# USB3_Interface.net
KiCad netlist of a schematic drawn in Altium Designer
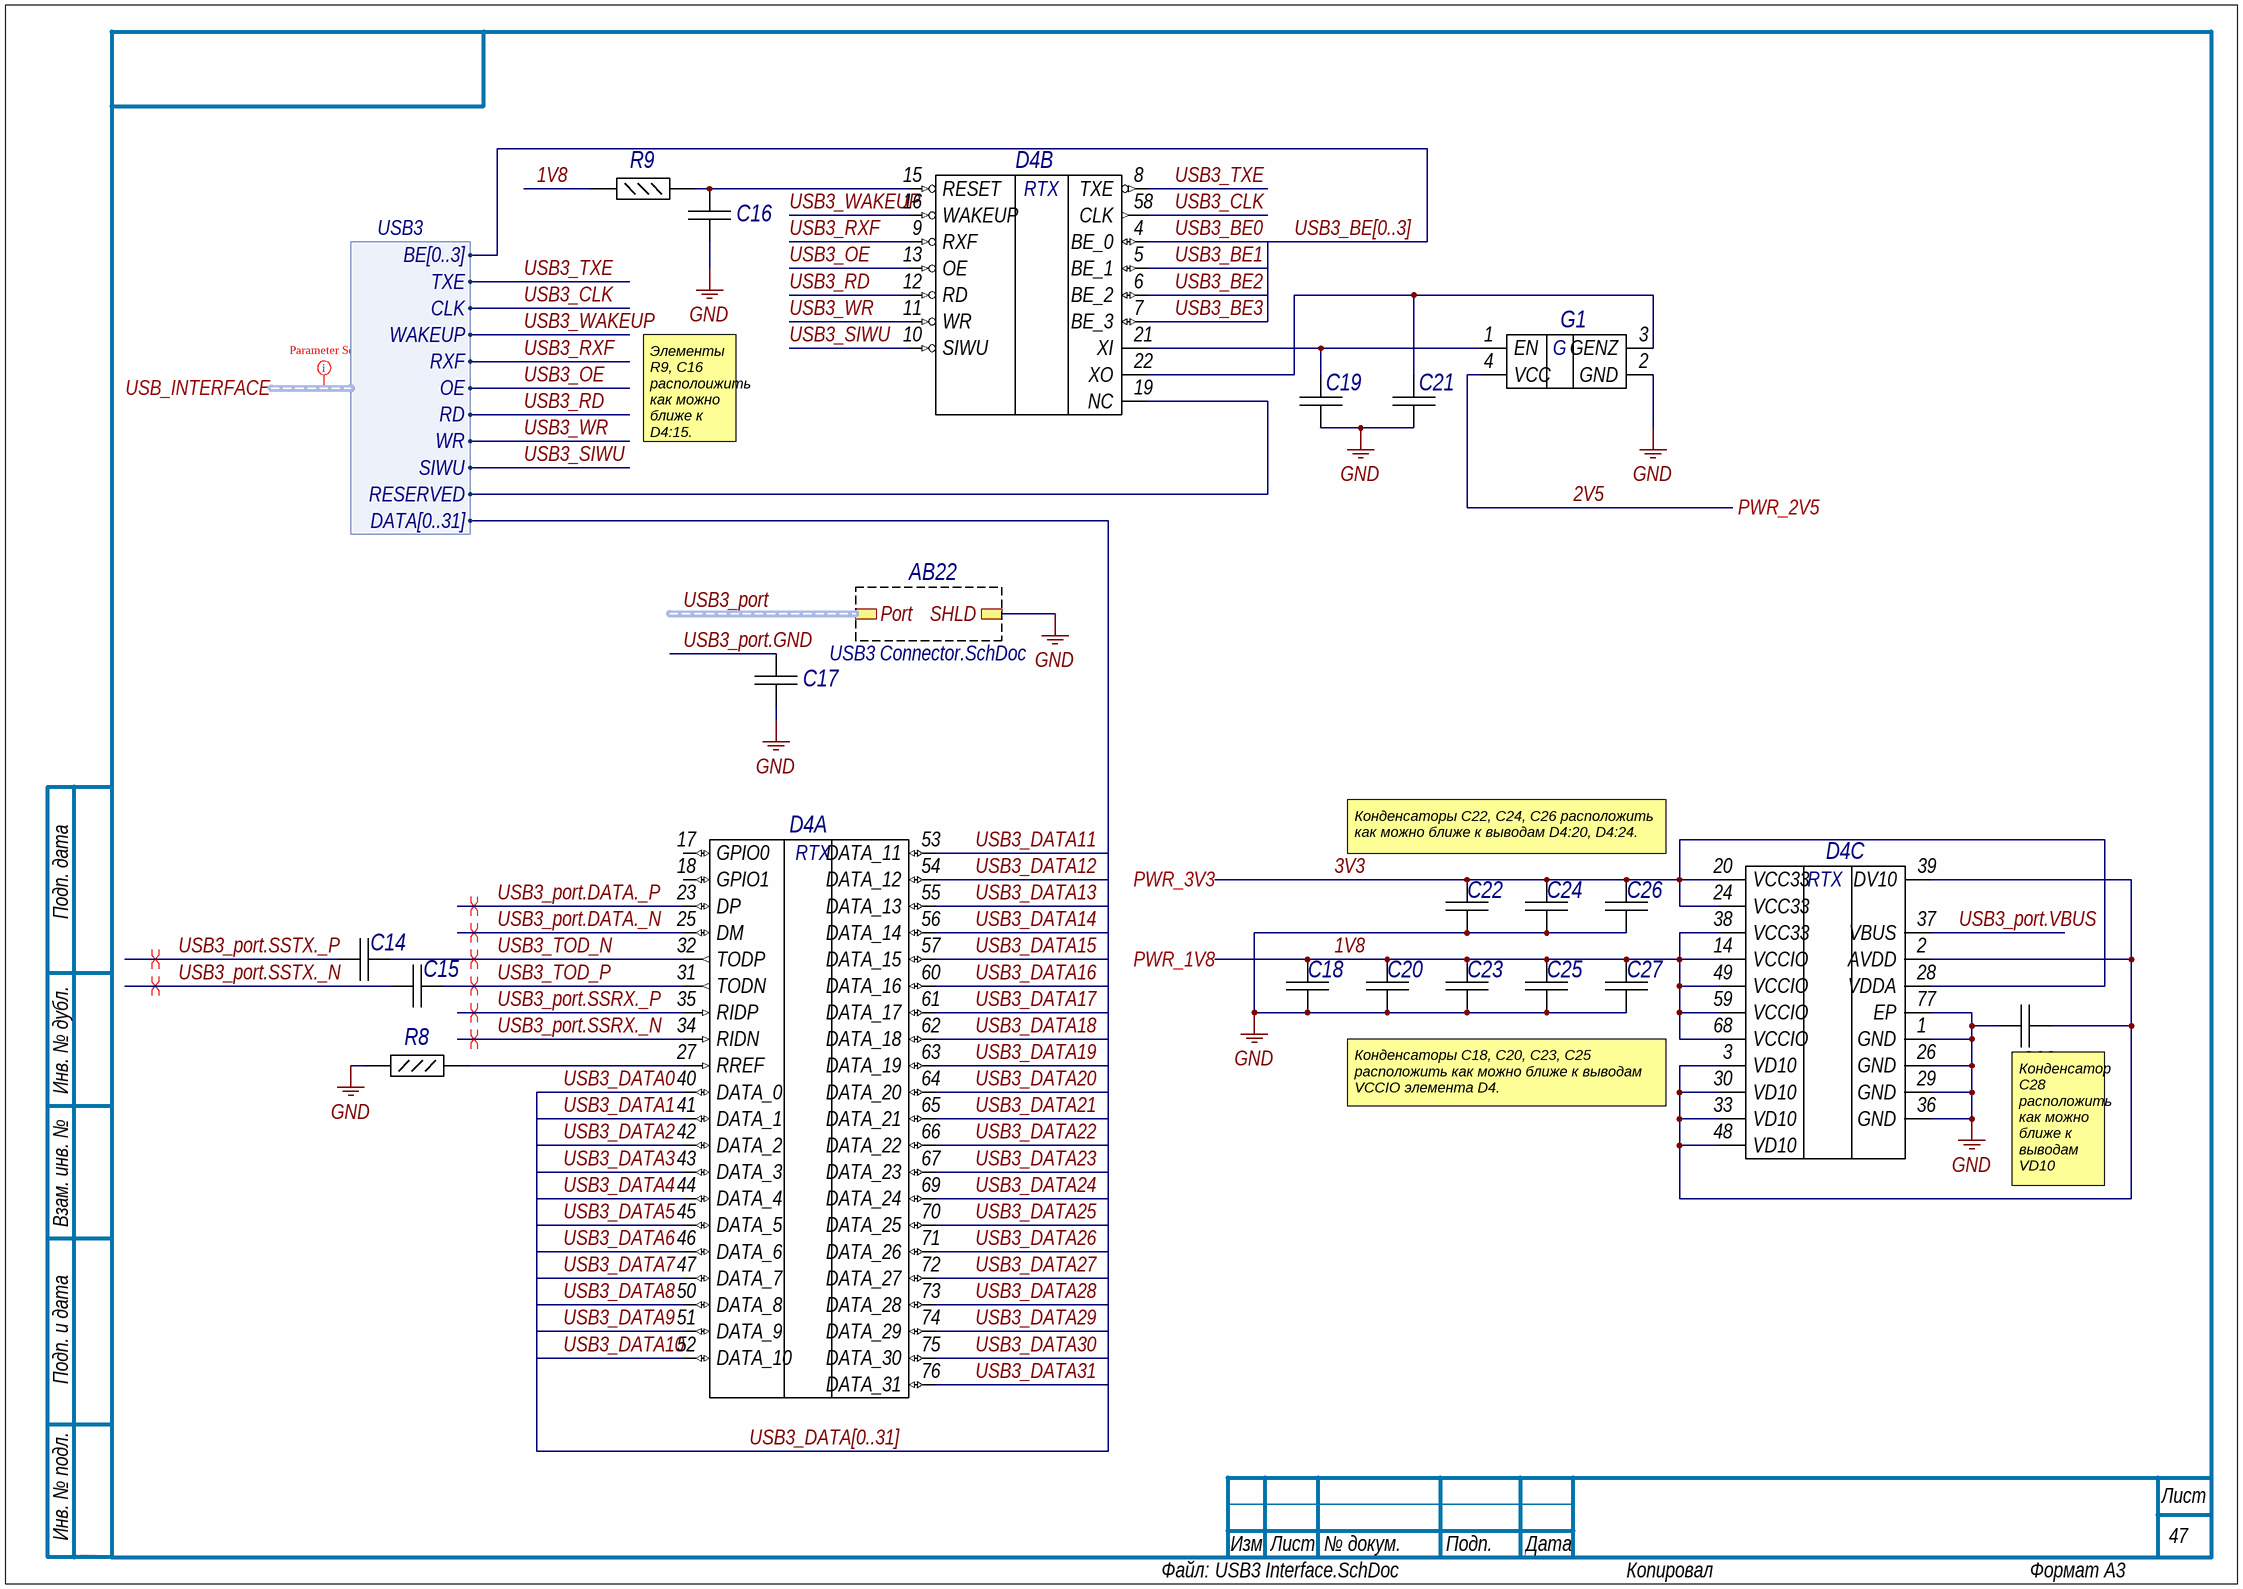
[diagram p0: USB3 Interface.SchDoc]

(export (version "E")
  (design (tool "Eeschema 10.0.6"))
  (components
    (comp (ref "C14")
      (value "GRM033R60J104KE19D")
      (footprint "CAPC0603X33X15LL03T05")
      (description "Chip Capacitor, 100 nF, +/- 10%, 6.3 V, -55 to 85 degC, 0201 (0603 Metric), RoHS, Tape and Reel")
      (fields (field (name "TOLERANCE") "10%") (field (name "MANUFACTURER") "Basic Passives"))
      (libsource (lib "MiniPC DB") (part "CAP_NP"))
    )
    (comp (ref "C15")
      (value "GRM033R60J104KE19D")
      (footprint "CAPC0603X33X15LL03T05")
      (description "Chip Capacitor, 100 nF, +/- 10%, 6.3 V, -55 to 85 degC, 0201 (0603 Metric), RoHS, Tape and Reel")
      (fields (field (name "TOLERANCE") "10%") (field (name "MANUFACTURER") "Basic Passives"))
      (libsource (lib "MiniPC DB") (part "CAP_NP"))
    )
    (comp (ref "C16")
      (value "GRM033R60J104KE19D")
      (footprint "CAPC0603X33X15LL03T05")
      (description "Chip Capacitor, 100 nF, +/- 10%, 6.3 V, -55 to 85 degC, 0201 (0603 Metric), RoHS, Tape and Reel")
      (fields (field (name "TOLERANCE") "10%") (field (name "MANUFACTURER") "Basic Passives"))
      (libsource (lib "MiniPC DB") (part "CAP_NP"))
    )
    (comp (ref "C17")
      (value "GRM033R60J104KE19D")
      (footprint "CAPC0603X33X15LL03T05")
      (description "Chip Capacitor, 100 nF, +/- 10%, 6.3 V, -55 to 85 degC, 0201 (0603 Metric), RoHS, Tape and Reel")
      (fields (field (name "TOLERANCE") "10%") (field (name "MANUFACTURER") "Basic Passives"))
      (libsource (lib "MiniPC DB") (part "CAP_NP"))
    )
    (comp (ref "C18")
      (value "C1005X7R1E104M")
      (footprint "CAPC1005X55X10LL05")
      (description "Chip Capacitor, 0.1 uF, +/- 20%, 25 V, -55 to 125 degC, 0402 (1005 Metric), RoHS, Tape and Reel")
      (fields (field (name "TOLERANCE") "20%"))
      (libsource (lib "MiniPC DB") (part "CAP_NP"))
    )
    (comp (ref "C19")
      (value "GRM033R60J104KE19D")
      (footprint "CAPC0603X33X15LL03T05")
      (description "Chip Capacitor, 100 nF, +/- 10%, 6.3 V, -55 to 85 degC, 0201 (0603 Metric), RoHS, Tape and Reel")
      (fields (field (name "TOLERANCE") "10%") (field (name "MANUFACTURER") "Basic Passives"))
      (libsource (lib "MiniPC DB") (part "CAP_NP"))
    )
    (comp (ref "C20")
      (value "C1005X7R1E104M")
      (footprint "CAPC1005X55X10LL05")
      (description "Chip Capacitor, 0.1 uF, +/- 20%, 25 V, -55 to 125 degC, 0402 (1005 Metric), RoHS, Tape and Reel")
      (fields (field (name "TOLERANCE") "20%"))
      (libsource (lib "MiniPC DB") (part "CAP_NP"))
    )
    (comp (ref "C21")
      (value "GRM033R60J104KE19D")
      (footprint "CAPC0603X33X15LL03T05")
      (description "Chip Capacitor, 100 nF, +/- 10%, 6.3 V, -55 to 85 degC, 0201 (0603 Metric), RoHS, Tape and Reel")
      (fields (field (name "TOLERANCE") "10%") (field (name "MANUFACTURER") "Basic Passives"))
      (libsource (lib "MiniPC DB") (part "CAP_NP"))
    )
    (comp (ref "C22")
      (value "C1005X7R1E104M")
      (footprint "CAPC1005X55X10LL05")
      (description "Chip Capacitor, 0.1 uF, +/- 20%, 25 V, -55 to 125 degC, 0402 (1005 Metric), RoHS, Tape and Reel")
      (fields (field (name "TOLERANCE") "20%"))
      (libsource (lib "MiniPC DB") (part "CAP_NP"))
    )
    (comp (ref "C23")
      (value "C1005X7R1E104M")
      (footprint "CAPC1005X55X10LL05")
      (description "Chip Capacitor, 0.1 uF, +/- 20%, 25 V, -55 to 125 degC, 0402 (1005 Metric), RoHS, Tape and Reel")
      (fields (field (name "TOLERANCE") "20%"))
      (libsource (lib "MiniPC DB") (part "CAP_NP"))
    )
    (comp (ref "C24")
      (value "C1005X7R1E104M")
      (footprint "CAPC1005X55X10LL05")
      (description "Chip Capacitor, 0.1 uF, +/- 20%, 25 V, -55 to 125 degC, 0402 (1005 Metric), RoHS, Tape and Reel")
      (fields (field (name "TOLERANCE") "20%"))
      (libsource (lib "MiniPC DB") (part "CAP_NP"))
    )
    (comp (ref "C25")
      (value "C1005X7R1E104M")
      (footprint "CAPC1005X55X10LL05")
      (description "Chip Capacitor, 0.1 uF, +/- 20%, 25 V, -55 to 125 degC, 0402 (1005 Metric), RoHS, Tape and Reel")
      (fields (field (name "TOLERANCE") "20%"))
      (libsource (lib "MiniPC DB") (part "CAP_NP"))
    )
    (comp (ref "C26")
      (value "C1005X7R1E104M")
      (footprint "CAPC1005X55X10LL05")
      (description "Chip Capacitor, 0.1 uF, +/- 20%, 25 V, -55 to 125 degC, 0402 (1005 Metric), RoHS, Tape and Reel")
      (fields (field (name "TOLERANCE") "20%"))
      (libsource (lib "MiniPC DB") (part "CAP_NP"))
    )
    (comp (ref "C27")
      (value "C1005X7R1E104M")
      (footprint "CAPC1005X55X10LL05")
      (description "Chip Capacitor, 0.1 uF, +/- 20%, 25 V, -55 to 125 degC, 0402 (1005 Metric), RoHS, Tape and Reel")
      (fields (field (name "TOLERANCE") "20%"))
      (libsource (lib "MiniPC DB") (part "CAP_NP"))
    )
    (comp (ref "C28")
      (value "GRM033R60J104KE19D")
      (footprint "CAPC0603X33X15LL03T05")
      (description "Chip Capacitor, 100 nF, +/- 10%, 6.3 V, -55 to 85 degC, 0201 (0603 Metric), RoHS, Tape and Reel")
      (fields (field (name "TOLERANCE") "10%") (field (name "MANUFACTURER") "Basic Passives"))
      (libsource (lib "MiniPC DB") (part "CAP_NP"))
    )
    (comp (ref "D4")
      (value "FT601Q")
      (footprint "FTDI-QFN-76_M")
      (description "32 Bit USB 3.0 to FIFO Bridge, 5 Gbps, 3 to 3.6 V, -40 to 85 degC, 76-Pin QFN, Pb-Free")
      (libsource (lib "") (part "FT601Q_1"))
    )
    (comp (ref "G1")
      (value "ASE2-33.000MHZ-ET")
      (footprint "ABRA-ASE2_V")
      (fields (field (name "MANUFACTURER") "Abracon"))
      (libsource (lib "MiniPC DB") (part "ASE2"))
    )
    (comp (ref "R8")
      (value "ERJ-2RKF1651X")
      (footprint "RESC1005X40X25LL05T05")
      (description "Chip Resistor, 1.65 KOhm, +/- 1%, 100 mW, -55 to 155 degC, 0402 (1005 Metric), RoHS, Tape and Reel")
      (fields (field (name "TOLERANCE") "1%") (field (name "MANUFACTURER") "Basic Passives"))
      (libsource (lib "") (part "RES-0.05_1"))
    )
    (comp (ref "R9")
      (value "ERJ-2RKF1002X")
      (footprint "RESC1005X40X25LL05T05")
      (description "Chip Resistor, 10 KOhm, +/- 1%, 100 mW, -55 to 155 degC, 0402 (1005 Metric), RoHS, Tape and Reel")
      (fields (field (name "TOLERANCE") "1%") (field (name "MANUFACTURER") "Basic Passives"))
      (libsource (lib "MiniPC DB") (part "RES-0.05"))
    )
  )
  (nets
    (net (code "3") (name "/1V8") (class "Default")
      (node (ref "C18") (pin "2") (pinfunction "2_2") (pintype "passive"))
      (node (ref "C20") (pin "2") (pinfunction "2_2") (pintype "passive"))
      (node (ref "C23") (pin "2") (pinfunction "2_2") (pintype "passive"))
      (node (ref "C25") (pin "2") (pinfunction "2_2") (pintype "passive"))
      (node (ref "C27") (pin "2") (pinfunction "2_2") (pintype "passive"))
      (node (ref "D4") (pin "14") (pinfunction "VCCIO_14") (pintype "power_in"))
      (node (ref "D4") (pin "38") (pinfunction "VCC33_38") (pintype "power_in"))
      (node (ref "D4") (pin "49") (pinfunction "VCCIO_49") (pintype "power_in"))
      (node (ref "D4") (pin "59") (pinfunction "VCCIO_59") (pintype "power_in"))
      (node (ref "D4") (pin "68") (pinfunction "VCCIO_68") (pintype "power_in"))
      (node (ref "R9") (pin "1") (pinfunction "1_1") (pintype "passive"))
    )
    (net (code "4") (name "/2V5") (class "Default")
      (node (ref "G1") (pin "4") (pinfunction "VCC_4") (pintype "passive"))
    )
    (net (code "5") (name "/3V3") (class "Default")
      (node (ref "C22") (pin "2") (pinfunction "2_2") (pintype "passive"))
      (node (ref "C24") (pin "2") (pinfunction "2_2") (pintype "passive"))
      (node (ref "C26") (pin "2") (pinfunction "2_2") (pintype "passive"))
      (node (ref "D4") (pin "20") (pinfunction "VCC33_20") (pintype "power_in"))
      (node (ref "D4") (pin "24") (pinfunction "VCC33_24") (pintype "power_in"))
      (node (ref "D4") (pin "28") (pinfunction "VDDA_28") (pintype "power_in"))
    )
    (net (code "6") (name "/RESERVED") (class "Default")
      (node (ref "D4") (pin "19") (pinfunction "NC_19") (pintype "passive"))
    )
    (net (code "7") (name "/USB3_BE0") (class "Default")
      (node (ref "D4") (pin "4") (pinfunction "BE_0_4") (pintype "bidirectional"))
    )
    (net (code "8") (name "/USB3_BE1") (class "Default")
      (node (ref "D4") (pin "5") (pinfunction "BE_1_5") (pintype "bidirectional"))
    )
    (net (code "9") (name "/USB3_BE2") (class "Default")
      (node (ref "D4") (pin "6") (pinfunction "BE_2_6") (pintype "bidirectional"))
    )
    (net (code "10") (name "/USB3_BE3") (class "Default")
      (node (ref "D4") (pin "7") (pinfunction "BE_3_7") (pintype "bidirectional"))
    )
    (net (code "12") (name "/USB3_CLK") (class "Default")
      (node (ref "D4") (pin "58") (pinfunction "CLK_58") (pintype "output"))
    )
    (net (code "13") (name "/USB3_DATA0") (class "Default")
      (node (ref "D4") (pin "40") (pinfunction "DATA_0_40") (pintype "bidirectional"))
    )
    (net (code "14") (name "/USB3_DATA1") (class "Default")
      (node (ref "D4") (pin "41") (pinfunction "DATA_1_41") (pintype "bidirectional"))
    )
    (net (code "15") (name "/USB3_DATA2") (class "Default")
      (node (ref "D4") (pin "42") (pinfunction "DATA_2_42") (pintype "bidirectional"))
    )
    (net (code "16") (name "/USB3_DATA3") (class "Default")
      (node (ref "D4") (pin "43") (pinfunction "DATA_3_43") (pintype "bidirectional"))
    )
    (net (code "17") (name "/USB3_DATA4") (class "Default")
      (node (ref "D4") (pin "44") (pinfunction "DATA_4_44") (pintype "bidirectional"))
    )
    (net (code "18") (name "/USB3_DATA5") (class "Default")
      (node (ref "D4") (pin "45") (pinfunction "DATA_5_45") (pintype "bidirectional"))
    )
    (net (code "19") (name "/USB3_DATA6") (class "Default")
      (node (ref "D4") (pin "46") (pinfunction "DATA_6_46") (pintype "bidirectional"))
    )
    (net (code "20") (name "/USB3_DATA7") (class "Default")
      (node (ref "D4") (pin "47") (pinfunction "DATA_7_47") (pintype "bidirectional"))
    )
    (net (code "21") (name "/USB3_DATA8") (class "Default")
      (node (ref "D4") (pin "50") (pinfunction "DATA_8_50") (pintype "bidirectional"))
    )
    (net (code "22") (name "/USB3_DATA9") (class "Default")
      (node (ref "D4") (pin "51") (pinfunction "DATA_9_51") (pintype "bidirectional"))
    )
    (net (code "23") (name "/USB3_DATA10") (class "Default")
      (node (ref "D4") (pin "52") (pinfunction "DATA_10_52") (pintype "bidirectional"))
    )
    (net (code "24") (name "/USB3_DATA11") (class "Default")
      (node (ref "D4") (pin "53") (pinfunction "DATA_11_53") (pintype "bidirectional"))
    )
    (net (code "25") (name "/USB3_DATA12") (class "Default")
      (node (ref "D4") (pin "54") (pinfunction "DATA_12_54") (pintype "bidirectional"))
    )
    (net (code "26") (name "/USB3_DATA13") (class "Default")
      (node (ref "D4") (pin "55") (pinfunction "DATA_13_55") (pintype "bidirectional"))
    )
    (net (code "27") (name "/USB3_DATA14") (class "Default")
      (node (ref "D4") (pin "56") (pinfunction "DATA_14_56") (pintype "bidirectional"))
    )
    (net (code "28") (name "/USB3_DATA15") (class "Default")
      (node (ref "D4") (pin "57") (pinfunction "DATA_15_57") (pintype "bidirectional"))
    )
    (net (code "29") (name "/USB3_DATA16") (class "Default")
      (node (ref "D4") (pin "60") (pinfunction "DATA_16_60") (pintype "bidirectional"))
    )
    (net (code "30") (name "/USB3_DATA17") (class "Default")
      (node (ref "D4") (pin "61") (pinfunction "DATA_17_61") (pintype "bidirectional"))
    )
    (net (code "31") (name "/USB3_DATA18") (class "Default")
      (node (ref "D4") (pin "62") (pinfunction "DATA_18_62") (pintype "bidirectional"))
    )
    (net (code "32") (name "/USB3_DATA19") (class "Default")
      (node (ref "D4") (pin "63") (pinfunction "DATA_19_63") (pintype "bidirectional"))
    )
    (net (code "33") (name "/USB3_DATA20") (class "Default")
      (node (ref "D4") (pin "64") (pinfunction "DATA_20_64") (pintype "bidirectional"))
    )
    (net (code "34") (name "/USB3_DATA21") (class "Default")
      (node (ref "D4") (pin "65") (pinfunction "DATA_21_65") (pintype "bidirectional"))
    )
    (net (code "35") (name "/USB3_DATA22") (class "Default")
      (node (ref "D4") (pin "66") (pinfunction "DATA_22_66") (pintype "bidirectional"))
    )
    (net (code "36") (name "/USB3_DATA23") (class "Default")
      (node (ref "D4") (pin "67") (pinfunction "DATA_23_67") (pintype "bidirectional"))
    )
    (net (code "37") (name "/USB3_DATA24") (class "Default")
      (node (ref "D4") (pin "69") (pinfunction "DATA_24_69") (pintype "bidirectional"))
    )
    (net (code "38") (name "/USB3_DATA25") (class "Default")
      (node (ref "D4") (pin "70") (pinfunction "DATA_25_70") (pintype "bidirectional"))
    )
    (net (code "39") (name "/USB3_DATA26") (class "Default")
      (node (ref "D4") (pin "71") (pinfunction "DATA_26_71") (pintype "bidirectional"))
    )
    (net (code "40") (name "/USB3_DATA27") (class "Default")
      (node (ref "D4") (pin "72") (pinfunction "DATA_27_72") (pintype "bidirectional"))
    )
    (net (code "41") (name "/USB3_DATA28") (class "Default")
      (node (ref "D4") (pin "73") (pinfunction "DATA_28_73") (pintype "bidirectional"))
    )
    (net (code "42") (name "/USB3_DATA29") (class "Default")
      (node (ref "D4") (pin "74") (pinfunction "DATA_29_74") (pintype "bidirectional"))
    )
    (net (code "43") (name "/USB3_DATA30") (class "Default")
      (node (ref "D4") (pin "75") (pinfunction "DATA_30_75") (pintype "bidirectional"))
    )
    (net (code "44") (name "/USB3_DATA31") (class "Default")
      (node (ref "D4") (pin "76") (pinfunction "DATA_31_76") (pintype "bidirectional"))
    )
    (net (code "45") (name "/USB3_OE") (class "Default")
      (node (ref "D4") (pin "13") (pinfunction "OE_13") (pintype "input"))
    )
    (net (code "46") (name "/USB3_RD") (class "Default")
      (node (ref "D4") (pin "12") (pinfunction "RD_12") (pintype "input"))
    )
    (net (code "47") (name "/USB3_RXF") (class "Default")
      (node (ref "D4") (pin "9") (pinfunction "RXF_9") (pintype "input"))
    )
    (net (code "48") (name "/USB3_SIWU") (class "Default")
      (node (ref "D4") (pin "10") (pinfunction "SIWU_10") (pintype "input"))
    )
    (net (code "49") (name "/USB3_TOD_N") (class "Default")
      (node (ref "C14") (pin "1") (pinfunction "1_1") (pintype "passive"))
      (node (ref "D4") (pin "32") (pinfunction "TODP_32") (pintype "output"))
    )
    (net (code "50") (name "/USB3_TOD_P") (class "Default")
      (node (ref "C15") (pin "1") (pinfunction "1_1") (pintype "passive"))
      (node (ref "D4") (pin "31") (pinfunction "TODN_31") (pintype "output"))
    )
    (net (code "51") (name "/USB3_TXE") (class "Default")
      (node (ref "D4") (pin "8") (pinfunction "TXE_8") (pintype "output"))
    )
    (net (code "52") (name "/USB3_WAKEUP") (class "Default")
      (node (ref "D4") (pin "16") (pinfunction "WAKEUP_16") (pintype "input"))
    )
    (net (code "53") (name "/USB3_WR") (class "Default")
      (node (ref "D4") (pin "11") (pinfunction "WR_11") (pintype "input"))
    )
    (net (code "54") (name "/USB3_port.DATA._N") (class "Default")
      (node (ref "D4") (pin "25") (pinfunction "DM_25") (pintype "bidirectional"))
    )
    (net (code "55") (name "/USB3_port.DATA._P") (class "Default")
      (node (ref "D4") (pin "23") (pinfunction "DP_23") (pintype "bidirectional"))
    )
    (net (code "56") (name "/USB3_port.GND") (class "Default")
      (node (ref "C17") (pin "2") (pinfunction "2_2") (pintype "passive"))
    )
    (net (code "57") (name "/USB3_port.SSRX._N") (class "Default")
      (node (ref "D4") (pin "34") (pinfunction "RIDN_34") (pintype "input"))
    )
    (net (code "58") (name "/USB3_port.SSRX._P") (class "Default")
      (node (ref "D4") (pin "35") (pinfunction "RIDP_35") (pintype "input"))
    )
    (net (code "59") (name "/USB3_port.SSTX._N") (class "Default")
      (node (ref "C15") (pin "2") (pinfunction "2_2") (pintype "passive"))
    )
    (net (code "60") (name "/USB3_port.SSTX._P") (class "Default")
      (node (ref "C14") (pin "2") (pinfunction "2_2") (pintype "passive"))
    )
    (net (code "61") (name "/USB3_port.VBUS") (class "Default")
      (node (ref "D4") (pin "37") (pinfunction "VBUS_37") (pintype "power_in"))
    )
    (net (code "65") (name "GND") (class "Default")
      (node (ref "C16") (pin "1") (pinfunction "1_1") (pintype "passive"))
      (node (ref "C17") (pin "1") (pinfunction "1_1") (pintype "passive"))
      (node (ref "C18") (pin "1") (pinfunction "1_1") (pintype "passive"))
      (node (ref "C19") (pin "1") (pinfunction "1_1") (pintype "passive"))
      (node (ref "C20") (pin "1") (pinfunction "1_1") (pintype "passive"))
      (node (ref "C21") (pin "1") (pinfunction "1_1") (pintype "passive"))
      (node (ref "C22") (pin "1") (pinfunction "1_1") (pintype "passive"))
      (node (ref "C23") (pin "1") (pinfunction "1_1") (pintype "passive"))
      (node (ref "C24") (pin "1") (pinfunction "1_1") (pintype "passive"))
      (node (ref "C25") (pin "1") (pinfunction "1_1") (pintype "passive"))
      (node (ref "C26") (pin "1") (pinfunction "1_1") (pintype "passive"))
      (node (ref "C27") (pin "1") (pinfunction "1_1") (pintype "passive"))
      (node (ref "C28") (pin "2") (pinfunction "2_2") (pintype "passive"))
      (node (ref "D4") (pin "1") (pinfunction "GND_1") (pintype "power_in"))
      (node (ref "D4") (pin "26") (pinfunction "GND_26") (pintype "power_in"))
      (node (ref "D4") (pin "29") (pinfunction "GND_29") (pintype "power_in"))
      (node (ref "D4") (pin "36") (pinfunction "GND_36") (pintype "power_in"))
      (node (ref "D4") (pin "77") (pinfunction "EP_77") (pintype "power_in"))
      (node (ref "G1") (pin "2") (pinfunction "GND_2") (pintype "passive"))
      (node (ref "R8") (pin "2") (pinfunction "2_2") (pintype "passive"))
    )
    (net (code "66") (name "Net-(D4A-RREF)") (class "Default")
      (node (ref "D4") (pin "27") (pinfunction "RREF_27") (pintype "input"))
      (node (ref "R8") (pin "1") (pinfunction "1_1") (pintype "passive"))
    )
    (net (code "67") (name "Net-(D4B-RESET)") (class "Default")
      (node (ref "C16") (pin "2") (pinfunction "2_2") (pintype "passive"))
      (node (ref "D4") (pin "15") (pinfunction "RESET_15") (pintype "input"))
      (node (ref "R9") (pin "2") (pinfunction "2_2") (pintype "passive"))
    )
    (net (code "68") (name "Net-(D4B-XI)") (class "Default")
      (node (ref "C19") (pin "2") (pinfunction "2_2") (pintype "passive"))
      (node (ref "D4") (pin "21") (pinfunction "XI_21") (pintype "passive"))
      (node (ref "G1") (pin "1") (pinfunction "EN_1") (pintype "passive"))
    )
    (net (code "69") (name "Net-(D4B-XO)") (class "Default")
      (node (ref "C21") (pin "2") (pinfunction "2_2") (pintype "passive"))
      (node (ref "D4") (pin "22") (pinfunction "XO_22") (pintype "passive"))
      (node (ref "G1") (pin "3") (pinfunction "GENZ_3") (pintype "passive"))
    )
    (net (code "70") (name "Net-(D4C-AVDD)") (class "Default")
      (node (ref "C28") (pin "1") (pinfunction "1_1") (pintype "passive"))
      (node (ref "D4") (pin "2") (pinfunction "AVDD_2") (pintype "power_in"))
      (node (ref "D4") (pin "3") (pinfunction "VD10_3") (pintype "power_in"))
      (node (ref "D4") (pin "30") (pinfunction "VD10_30") (pintype "power_in"))
      (node (ref "D4") (pin "33") (pinfunction "VD10_33") (pintype "power_in"))
      (node (ref "D4") (pin "39") (pinfunction "DV10_39") (pintype "power_in"))
      (node (ref "D4") (pin "48") (pinfunction "VD10_48") (pintype "power_in"))
    )
    (net (code "71") (name "unconnected-(D4A-GPIO0-Pad17)") (class "Default")
      (node (ref "D4") (pin "17") (pinfunction "GPIO0_17") (pintype "bidirectional"))
    )
    (net (code "72") (name "unconnected-(D4A-GPIO1-Pad18)") (class "Default")
      (node (ref "D4") (pin "18") (pinfunction "GPIO1_18") (pintype "bidirectional"))
    )
  )
)
